# Sonar_2012_V9.net
KiCad netlist of a schematic drawn in EAGLE
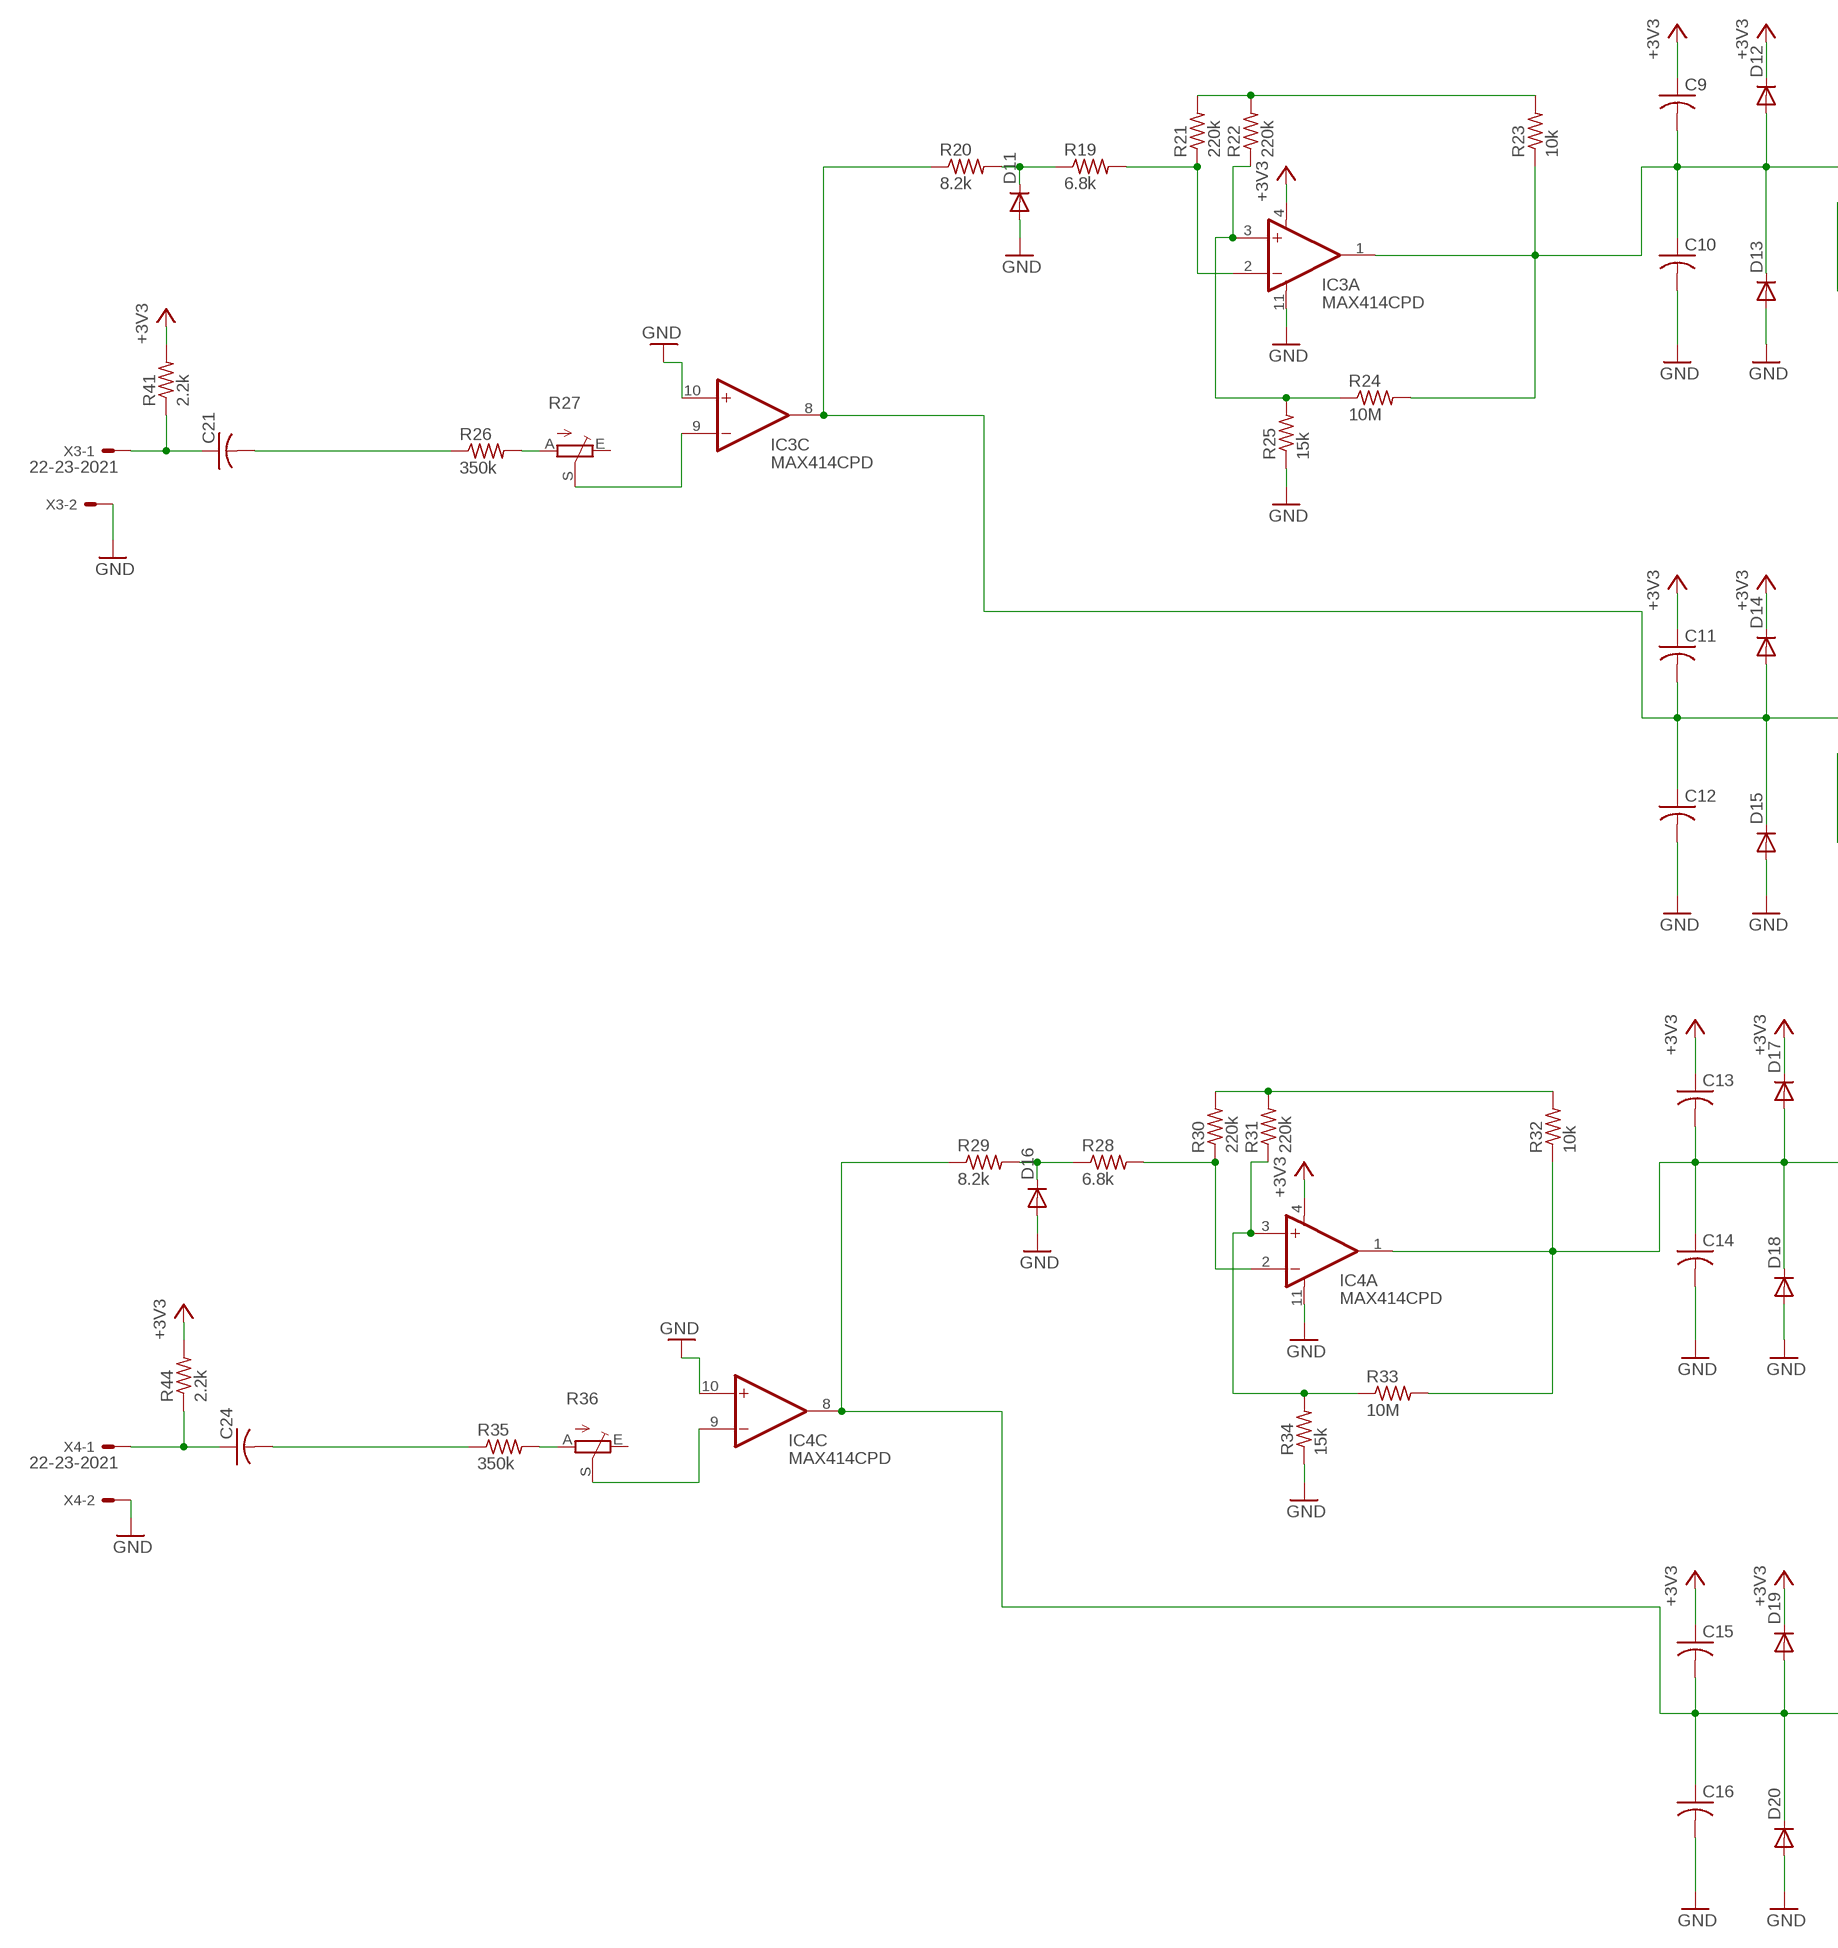
[diagram p0: schematic, sheet 1, part 1 of 2]
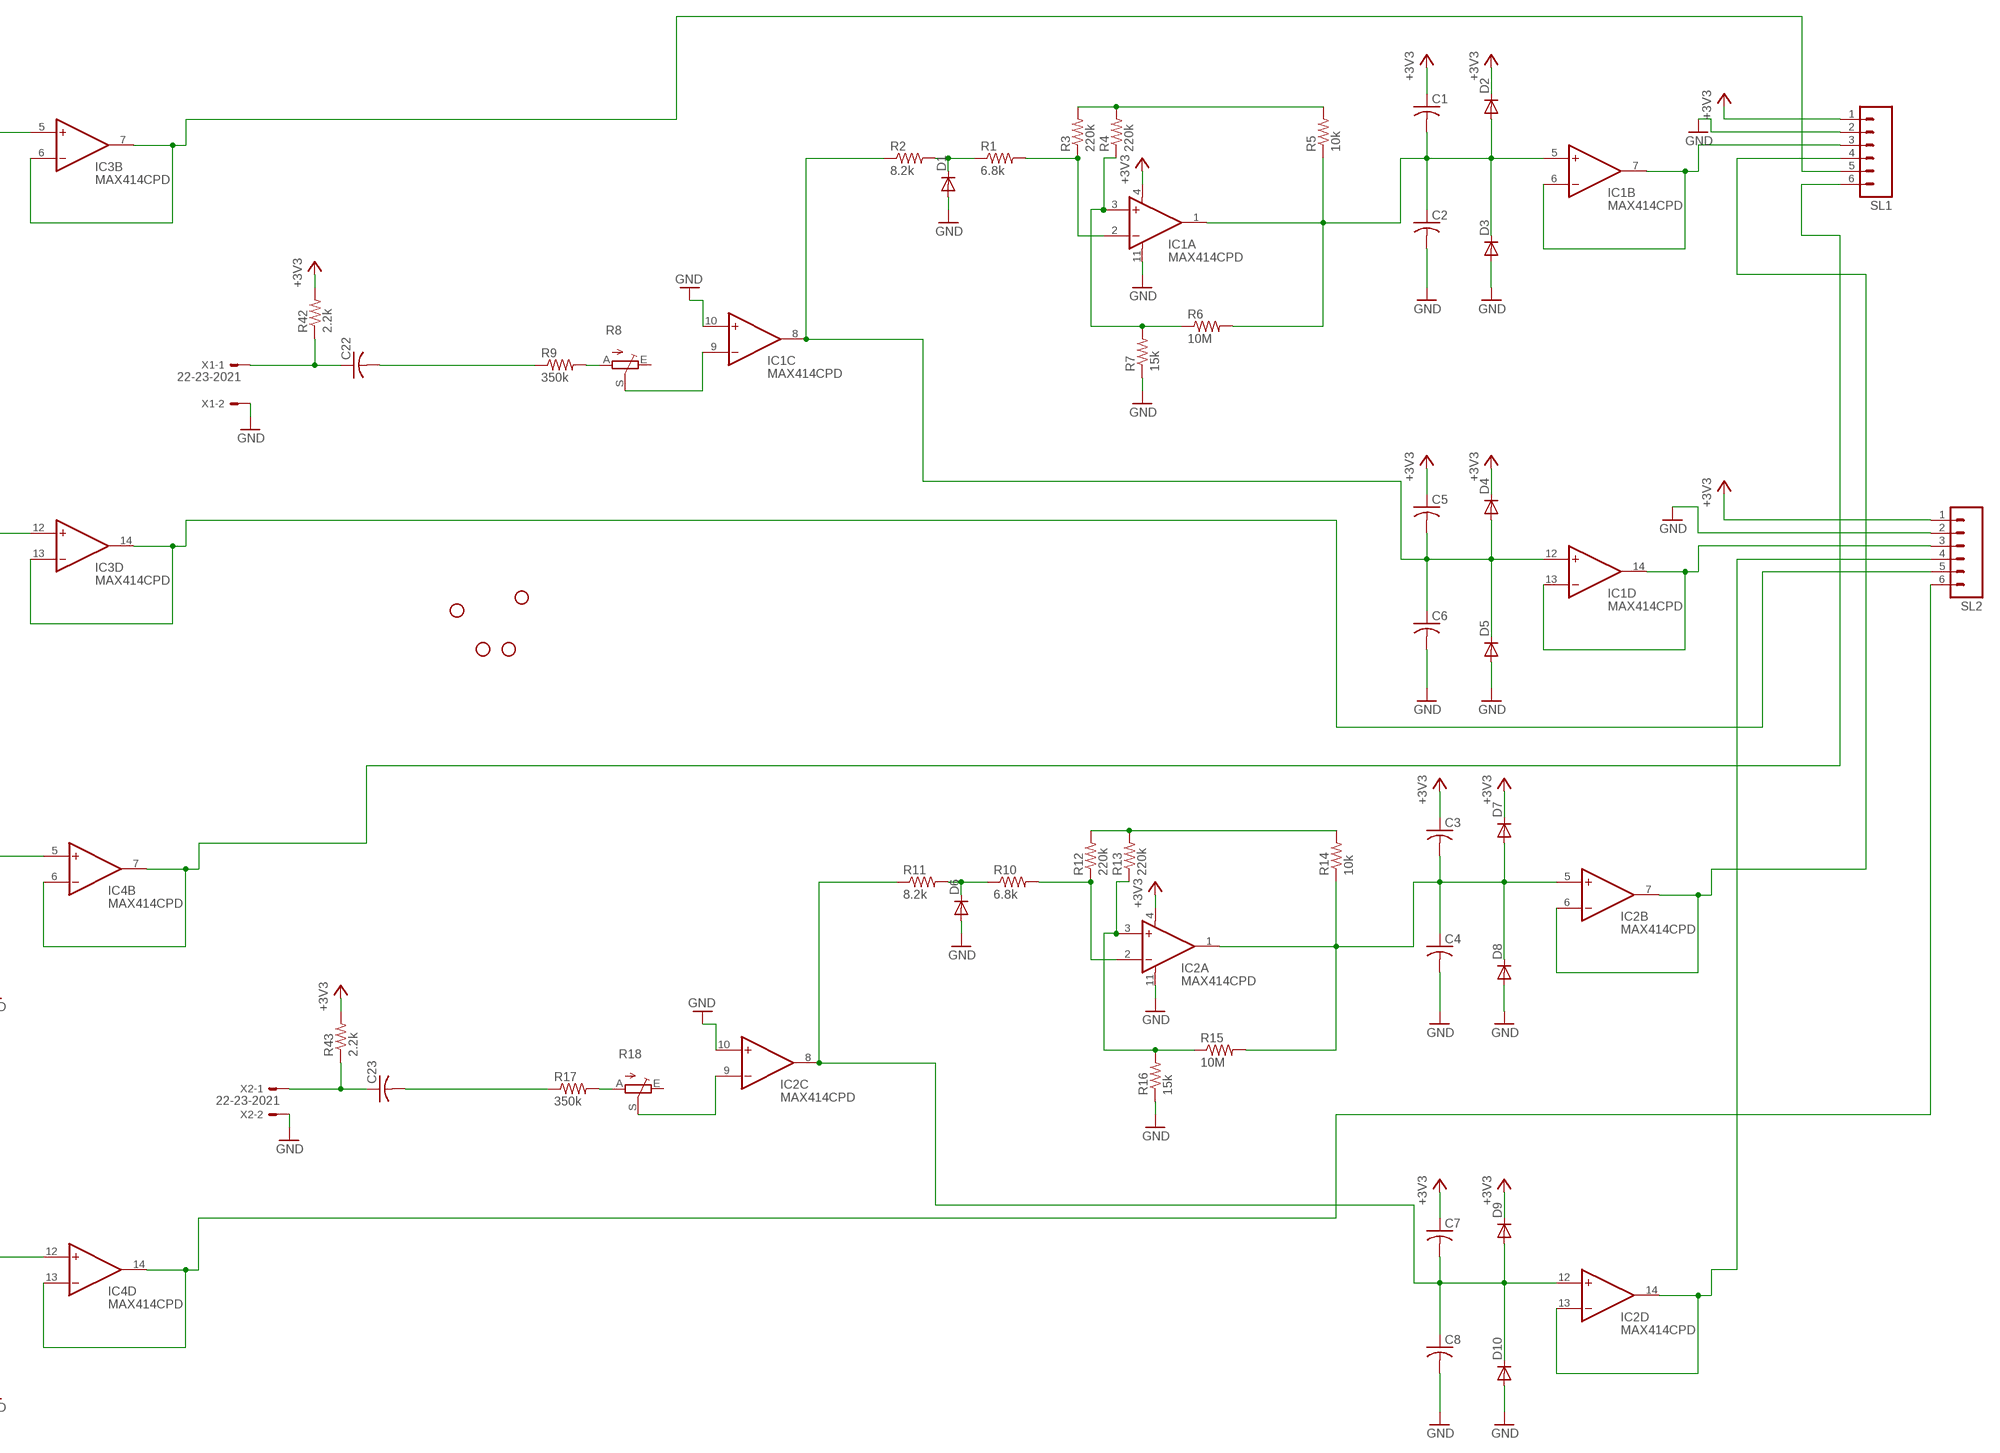
[diagram p1: schematic, sheet 1, part 2 of 2]

(export (version "E")
  (design (tool "Eeschema 10.0.6"))
  (components
    (comp (ref "C1")
      (value "C-USC0603")
      (footprint "eagle-import:C0603")
      (libsource (lib "eagle-import") (part "C-USC0603"))
    )
    (comp (ref "C2")
      (value "C-USC0603")
      (footprint "eagle-import:C0603")
      (libsource (lib "eagle-import") (part "C-USC0603"))
    )
    (comp (ref "C3")
      (value "C-USC0603")
      (footprint "eagle-import:C0603")
      (libsource (lib "eagle-import") (part "C-USC0603"))
    )
    (comp (ref "C4")
      (value "C-USC0603")
      (footprint "eagle-import:C0603")
      (libsource (lib "eagle-import") (part "C-USC0603"))
    )
    (comp (ref "C5")
      (value "C-USC0603")
      (footprint "eagle-import:C0603")
      (libsource (lib "eagle-import") (part "C-USC0603"))
    )
    (comp (ref "C6")
      (value "C-USC0603")
      (footprint "eagle-import:C0603")
      (libsource (lib "eagle-import") (part "C-USC0603"))
    )
    (comp (ref "C7")
      (value "C-USC0603")
      (footprint "eagle-import:C0603")
      (libsource (lib "eagle-import") (part "C-USC0603"))
    )
    (comp (ref "C8")
      (value "C-USC0603")
      (footprint "eagle-import:C0603")
      (libsource (lib "eagle-import") (part "C-USC0603"))
    )
    (comp (ref "C9")
      (value "C-USC0603")
      (footprint "eagle-import:C0603")
      (libsource (lib "eagle-import") (part "C-USC0603"))
    )
    (comp (ref "C10")
      (value "C-USC0603")
      (footprint "eagle-import:C0603")
      (libsource (lib "eagle-import") (part "C-USC0603"))
    )
    (comp (ref "C11")
      (value "C-USC0603")
      (footprint "eagle-import:C0603")
      (libsource (lib "eagle-import") (part "C-USC0603"))
    )
    (comp (ref "C12")
      (value "C-USC0603")
      (footprint "eagle-import:C0603")
      (libsource (lib "eagle-import") (part "C-USC0603"))
    )
    (comp (ref "C13")
      (value "C-USC0603")
      (footprint "eagle-import:C0603")
      (libsource (lib "eagle-import") (part "C-USC0603"))
    )
    (comp (ref "C14")
      (value "C-USC0603")
      (footprint "eagle-import:C0603")
      (libsource (lib "eagle-import") (part "C-USC0603"))
    )
    (comp (ref "C15")
      (value "C-USC0603")
      (footprint "eagle-import:C0603")
      (libsource (lib "eagle-import") (part "C-USC0603"))
    )
    (comp (ref "C16")
      (value "C-USC0603")
      (footprint "eagle-import:C0603")
      (libsource (lib "eagle-import") (part "C-USC0603"))
    )
    (comp (ref "C21")
      (value "C-USC0603")
      (footprint "eagle-import:C0603")
      (libsource (lib "eagle-import") (part "C-USC0603"))
    )
    (comp (ref "C22")
      (value "C-USC0603")
      (footprint "eagle-import:C0603")
      (libsource (lib "eagle-import") (part "C-USC0603"))
    )
    (comp (ref "C23")
      (value "C-USC0603")
      (footprint "eagle-import:C0603")
      (libsource (lib "eagle-import") (part "C-USC0603"))
    )
    (comp (ref "C24")
      (value "C-USC0603")
      (footprint "eagle-import:C0603")
      (libsource (lib "eagle-import") (part "C-USC0603"))
    )
    (comp (ref "D1")
      (value "DIODE-SOD523")
      (footprint "eagle-import:SOD523")
      (libsource (lib "eagle-import") (part "DIODE-SOD523"))
    )
    (comp (ref "D2")
      (value "DIODE-SOD523")
      (footprint "eagle-import:SOD523")
      (libsource (lib "eagle-import") (part "DIODE-SOD523"))
    )
    (comp (ref "D3")
      (value "DIODE-SOD523")
      (footprint "eagle-import:SOD523")
      (libsource (lib "eagle-import") (part "DIODE-SOD523"))
    )
    (comp (ref "D4")
      (value "DIODE-SOD523")
      (footprint "eagle-import:SOD523")
      (libsource (lib "eagle-import") (part "DIODE-SOD523"))
    )
    (comp (ref "D5")
      (value "DIODE-SOD523")
      (footprint "eagle-import:SOD523")
      (libsource (lib "eagle-import") (part "DIODE-SOD523"))
    )
    (comp (ref "D6")
      (value "DIODE-SOD523")
      (footprint "eagle-import:SOD523")
      (libsource (lib "eagle-import") (part "DIODE-SOD523"))
    )
    (comp (ref "D7")
      (value "DIODE-SOD523")
      (footprint "eagle-import:SOD523")
      (libsource (lib "eagle-import") (part "DIODE-SOD523"))
    )
    (comp (ref "D8")
      (value "DIODE-SOD523")
      (footprint "eagle-import:SOD523")
      (libsource (lib "eagle-import") (part "DIODE-SOD523"))
    )
    (comp (ref "D9")
      (value "DIODE-SOD523")
      (footprint "eagle-import:SOD523")
      (libsource (lib "eagle-import") (part "DIODE-SOD523"))
    )
    (comp (ref "D10")
      (value "DIODE-SOD523")
      (footprint "eagle-import:SOD523")
      (libsource (lib "eagle-import") (part "DIODE-SOD523"))
    )
    (comp (ref "D11")
      (value "DIODE-SOD523")
      (footprint "eagle-import:SOD523")
      (libsource (lib "eagle-import") (part "DIODE-SOD523"))
    )
    (comp (ref "D12")
      (value "DIODE-SOD523")
      (footprint "eagle-import:SOD523")
      (libsource (lib "eagle-import") (part "DIODE-SOD523"))
    )
    (comp (ref "D13")
      (value "DIODE-SOD523")
      (footprint "eagle-import:SOD523")
      (libsource (lib "eagle-import") (part "DIODE-SOD523"))
    )
    (comp (ref "D14")
      (value "DIODE-SOD523")
      (footprint "eagle-import:SOD523")
      (libsource (lib "eagle-import") (part "DIODE-SOD523"))
    )
    (comp (ref "D15")
      (value "DIODE-SOD523")
      (footprint "eagle-import:SOD523")
      (libsource (lib "eagle-import") (part "DIODE-SOD523"))
    )
    (comp (ref "D16")
      (value "DIODE-SOD523")
      (footprint "eagle-import:SOD523")
      (libsource (lib "eagle-import") (part "DIODE-SOD523"))
    )
    (comp (ref "D17")
      (value "DIODE-SOD523")
      (footprint "eagle-import:SOD523")
      (libsource (lib "eagle-import") (part "DIODE-SOD523"))
    )
    (comp (ref "D18")
      (value "DIODE-SOD523")
      (footprint "eagle-import:SOD523")
      (libsource (lib "eagle-import") (part "DIODE-SOD523"))
    )
    (comp (ref "D19")
      (value "DIODE-SOD523")
      (footprint "eagle-import:SOD523")
      (libsource (lib "eagle-import") (part "DIODE-SOD523"))
    )
    (comp (ref "D20")
      (value "DIODE-SOD523")
      (footprint "eagle-import:SOD523")
      (libsource (lib "eagle-import") (part "DIODE-SOD523"))
    )
    (comp (ref "IC1")
      (value "MAX414CPD")
      (footprint "eagle-import:DIL14")
      (fields (field (name "MPN") "MAX414CPD+"))
      (libsource (lib "eagle-import") (part "MAX414CPD"))
    )
    (comp (ref "IC2")
      (value "MAX414CPD")
      (footprint "eagle-import:DIL14")
      (fields (field (name "MPN") "MAX414CPD+"))
      (libsource (lib "eagle-import") (part "MAX414CPD"))
    )
    (comp (ref "IC3")
      (value "MAX414CPD")
      (footprint "eagle-import:DIL14")
      (fields (field (name "MPN") "MAX414CPD+"))
      (libsource (lib "eagle-import") (part "MAX414CPD"))
    )
    (comp (ref "IC4")
      (value "MAX414CPD")
      (footprint "eagle-import:DIL14")
      (fields (field (name "MPN") "MAX414CPD+"))
      (libsource (lib "eagle-import") (part "MAX414CPD"))
    )
    (comp (ref "JP1")
      (value "STAND-OFF")
      (footprint "eagle-import:STAND-OFF")
      (libsource (lib "eagle-import") (part "STAND-OFF"))
    )
    (comp (ref "JP2")
      (value "STAND-OFF")
      (footprint "eagle-import:STAND-OFF")
      (libsource (lib "eagle-import") (part "STAND-OFF"))
    )
    (comp (ref "JP3")
      (value "STAND-OFF")
      (footprint "eagle-import:STAND-OFF")
      (libsource (lib "eagle-import") (part "STAND-OFF"))
    )
    (comp (ref "JP4")
      (value "STAND-OFF")
      (footprint "eagle-import:STAND-OFF")
      (libsource (lib "eagle-import") (part "STAND-OFF"))
    )
    (comp (ref "R1")
      (value "6.8k")
      (footprint "eagle-import:M1206")
      (libsource (lib "eagle-import") (part "R-US_M1206"))
    )
    (comp (ref "R2")
      (value "8.2k")
      (footprint "eagle-import:M1206")
      (libsource (lib "eagle-import") (part "R-US_M1206"))
    )
    (comp (ref "R3")
      (value "220k")
      (footprint "eagle-import:M1206")
      (libsource (lib "eagle-import") (part "R-US_M1206"))
    )
    (comp (ref "R4")
      (value "220k")
      (footprint "eagle-import:M1206")
      (libsource (lib "eagle-import") (part "R-US_M1206"))
    )
    (comp (ref "R5")
      (value "10k")
      (footprint "eagle-import:M1206")
      (libsource (lib "eagle-import") (part "R-US_M1206"))
    )
    (comp (ref "R6")
      (value "10M")
      (footprint "eagle-import:M1206")
      (libsource (lib "eagle-import") (part "R-US_M1206"))
    )
    (comp (ref "R7")
      (value "15k")
      (footprint "eagle-import:M1206")
      (libsource (lib "eagle-import") (part "R-US_M1206"))
    )
    (comp (ref "R8")
      (value "TRIM_EU-B64Y")
      (footprint "eagle-import:B64Y")
      (libsource (lib "eagle-import") (part "TRIM_EU-B64Y"))
    )
    (comp (ref "R9")
      (value "350k")
      (footprint "eagle-import:M1206")
      (libsource (lib "eagle-import") (part "R-US_M1206"))
    )
    (comp (ref "R10")
      (value "6.8k")
      (footprint "eagle-import:M1206")
      (libsource (lib "eagle-import") (part "R-US_M1206"))
    )
    (comp (ref "R11")
      (value "8.2k")
      (footprint "eagle-import:M1206")
      (libsource (lib "eagle-import") (part "R-US_M1206"))
    )
    (comp (ref "R12")
      (value "220k")
      (footprint "eagle-import:M1206")
      (libsource (lib "eagle-import") (part "R-US_M1206"))
    )
    (comp (ref "R13")
      (value "220k")
      (footprint "eagle-import:M1206")
      (libsource (lib "eagle-import") (part "R-US_M1206"))
    )
    (comp (ref "R14")
      (value "10k")
      (footprint "eagle-import:M1206")
      (libsource (lib "eagle-import") (part "R-US_M1206"))
    )
    (comp (ref "R15")
      (value "10M")
      (footprint "eagle-import:M1206")
      (libsource (lib "eagle-import") (part "R-US_M1206"))
    )
    (comp (ref "R16")
      (value "15k")
      (footprint "eagle-import:M1206")
      (libsource (lib "eagle-import") (part "R-US_M1206"))
    )
    (comp (ref "R17")
      (value "350k")
      (footprint "eagle-import:M1206")
      (libsource (lib "eagle-import") (part "R-US_M1206"))
    )
    (comp (ref "R18")
      (value "TRIM_EU-B64Y")
      (footprint "eagle-import:B64Y")
      (libsource (lib "eagle-import") (part "TRIM_EU-B64Y"))
    )
    (comp (ref "R19")
      (value "6.8k")
      (footprint "eagle-import:M1206")
      (libsource (lib "eagle-import") (part "R-US_M1206"))
    )
    (comp (ref "R20")
      (value "8.2k")
      (footprint "eagle-import:M1206")
      (libsource (lib "eagle-import") (part "R-US_M1206"))
    )
    (comp (ref "R21")
      (value "220k")
      (footprint "eagle-import:M1206")
      (libsource (lib "eagle-import") (part "R-US_M1206"))
    )
    (comp (ref "R22")
      (value "220k")
      (footprint "eagle-import:M1206")
      (libsource (lib "eagle-import") (part "R-US_M1206"))
    )
    (comp (ref "R23")
      (value "10k")
      (footprint "eagle-import:M1206")
      (libsource (lib "eagle-import") (part "R-US_M1206"))
    )
    (comp (ref "R24")
      (value "10M")
      (footprint "eagle-import:M1206")
      (libsource (lib "eagle-import") (part "R-US_M1206"))
    )
    (comp (ref "R25")
      (value "15k")
      (footprint "eagle-import:M1206")
      (libsource (lib "eagle-import") (part "R-US_M1206"))
    )
    (comp (ref "R26")
      (value "350k")
      (footprint "eagle-import:M1206")
      (libsource (lib "eagle-import") (part "R-US_M1206"))
    )
    (comp (ref "R27")
      (value "TRIM_EU-B64Y")
      (footprint "eagle-import:B64Y")
      (libsource (lib "eagle-import") (part "TRIM_EU-B64Y"))
    )
    (comp (ref "R28")
      (value "6.8k")
      (footprint "eagle-import:M1206")
      (libsource (lib "eagle-import") (part "R-US_M1206"))
    )
    (comp (ref "R29")
      (value "8.2k")
      (footprint "eagle-import:M1206")
      (libsource (lib "eagle-import") (part "R-US_M1206"))
    )
    (comp (ref "R30")
      (value "220k")
      (footprint "eagle-import:M1206")
      (libsource (lib "eagle-import") (part "R-US_M1206"))
    )
    (comp (ref "R31")
      (value "220k")
      (footprint "eagle-import:M1206")
      (libsource (lib "eagle-import") (part "R-US_M1206"))
    )
    (comp (ref "R32")
      (value "10k")
      (footprint "eagle-import:M1206")
      (libsource (lib "eagle-import") (part "R-US_M1206"))
    )
    (comp (ref "R33")
      (value "10M")
      (footprint "eagle-import:M1206")
      (libsource (lib "eagle-import") (part "R-US_M1206"))
    )
    (comp (ref "R34")
      (value "15k")
      (footprint "eagle-import:M1206")
      (libsource (lib "eagle-import") (part "R-US_M1206"))
    )
    (comp (ref "R35")
      (value "350k")
      (footprint "eagle-import:M1206")
      (libsource (lib "eagle-import") (part "R-US_M1206"))
    )
    (comp (ref "R36")
      (value "TRIM_EU-B64Y")
      (footprint "eagle-import:B64Y")
      (libsource (lib "eagle-import") (part "TRIM_EU-B64Y"))
    )
    (comp (ref "R41")
      (value "2.2k")
      (footprint "eagle-import:M1206")
      (libsource (lib "eagle-import") (part "R-US_M1206"))
    )
    (comp (ref "R42")
      (value "2.2k")
      (footprint "eagle-import:M1206")
      (libsource (lib "eagle-import") (part "R-US_M1206"))
    )
    (comp (ref "R43")
      (value "2.2k")
      (footprint "eagle-import:M1206")
      (libsource (lib "eagle-import") (part "R-US_M1206"))
    )
    (comp (ref "R44")
      (value "2.2k")
      (footprint "eagle-import:M1206")
      (libsource (lib "eagle-import") (part "R-US_M1206"))
    )
    (comp (ref "SL1")
      (value "M06")
      (footprint "eagle-import:06P")
      (libsource (lib "eagle-import") (part "M06"))
    )
    (comp (ref "SL2")
      (value "M06")
      (footprint "eagle-import:06P")
      (libsource (lib "eagle-import") (part "M06"))
    )
    (comp (ref "X1")
      (value "22-23-2021")
      (footprint "eagle-import:22-23-2021")
      (fields (field (name "MF") "MOLEX"))
      (libsource (lib "eagle-import") (part "22-23-2021"))
    )
    (comp (ref "X2")
      (value "22-23-2021")
      (footprint "eagle-import:22-23-2021")
      (fields (field (name "MF") "MOLEX"))
      (libsource (lib "eagle-import") (part "22-23-2021"))
    )
    (comp (ref "X3")
      (value "22-23-2021")
      (footprint "eagle-import:22-23-2021")
      (fields (field (name "MF") "MOLEX"))
      (libsource (lib "eagle-import") (part "22-23-2021"))
    )
    (comp (ref "X4")
      (value "22-23-2021")
      (footprint "eagle-import:22-23-2021")
      (fields (field (name "MF") "MOLEX"))
      (libsource (lib "eagle-import") (part "22-23-2021"))
    )
  )
  (nets
    (net (code "1") (name "+3V3") (class "Default")
      (node (ref "C1") (pin "1") (pinfunction "1_1") (pintype "passive"))
      (node (ref "C11") (pin "1") (pinfunction "1_1") (pintype "passive"))
      (node (ref "C13") (pin "1") (pinfunction "1_1") (pintype "passive"))
      (node (ref "C15") (pin "1") (pinfunction "1_1") (pintype "passive"))
      (node (ref "C3") (pin "1") (pinfunction "1_1") (pintype "passive"))
      (node (ref "C5") (pin "1") (pinfunction "1_1") (pintype "passive"))
      (node (ref "C7") (pin "1") (pinfunction "1_1") (pintype "passive"))
      (node (ref "C9") (pin "1") (pinfunction "1_1") (pintype "passive"))
      (node (ref "D12") (pin "C") (pinfunction "C_C") (pintype "passive"))
      (node (ref "D14") (pin "C") (pinfunction "C_C") (pintype "passive"))
      (node (ref "D17") (pin "C") (pinfunction "C_C") (pintype "passive"))
      (node (ref "D19") (pin "C") (pinfunction "C_C") (pintype "passive"))
      (node (ref "D2") (pin "C") (pinfunction "C_C") (pintype "passive"))
      (node (ref "D4") (pin "C") (pinfunction "C_C") (pintype "passive"))
      (node (ref "D7") (pin "C") (pinfunction "C_C") (pintype "passive"))
      (node (ref "D9") (pin "C") (pinfunction "C_C") (pintype "passive"))
      (node (ref "IC1") (pin "4") (pinfunction "V+_4") (pintype "power_in"))
      (node (ref "IC2") (pin "4") (pinfunction "V+_4") (pintype "power_in"))
      (node (ref "IC3") (pin "4") (pinfunction "V+_4") (pintype "power_in"))
      (node (ref "IC4") (pin "4") (pinfunction "V+_4") (pintype "power_in"))
      (node (ref "R41") (pin "2") (pinfunction "2_2") (pintype "passive"))
      (node (ref "R42") (pin "2") (pinfunction "2_2") (pintype "passive"))
      (node (ref "R43") (pin "2") (pinfunction "2_2") (pintype "passive"))
      (node (ref "R44") (pin "2") (pinfunction "2_2") (pintype "passive"))
      (node (ref "SL1") (pin "1") (pinfunction "1_1") (pintype "passive"))
      (node (ref "SL2") (pin "1") (pinfunction "1_1") (pintype "passive"))
    )
    (net (code "2") (name "GND") (class "Default")
      (node (ref "C10") (pin "2") (pinfunction "2_2") (pintype "passive"))
      (node (ref "C12") (pin "2") (pinfunction "2_2") (pintype "passive"))
      (node (ref "C14") (pin "2") (pinfunction "2_2") (pintype "passive"))
      (node (ref "C16") (pin "2") (pinfunction "2_2") (pintype "passive"))
      (node (ref "C2") (pin "2") (pinfunction "2_2") (pintype "passive"))
      (node (ref "C4") (pin "2") (pinfunction "2_2") (pintype "passive"))
      (node (ref "C6") (pin "2") (pinfunction "2_2") (pintype "passive"))
      (node (ref "C8") (pin "2") (pinfunction "2_2") (pintype "passive"))
      (node (ref "D1") (pin "A") (pinfunction "A_A") (pintype "passive"))
      (node (ref "D10") (pin "A") (pinfunction "A_A") (pintype "passive"))
      (node (ref "D11") (pin "A") (pinfunction "A_A") (pintype "passive"))
      (node (ref "D13") (pin "A") (pinfunction "A_A") (pintype "passive"))
      (node (ref "D15") (pin "A") (pinfunction "A_A") (pintype "passive"))
      (node (ref "D16") (pin "A") (pinfunction "A_A") (pintype "passive"))
      (node (ref "D18") (pin "A") (pinfunction "A_A") (pintype "passive"))
      (node (ref "D20") (pin "A") (pinfunction "A_A") (pintype "passive"))
      (node (ref "D3") (pin "A") (pinfunction "A_A") (pintype "passive"))
      (node (ref "D5") (pin "A") (pinfunction "A_A") (pintype "passive"))
      (node (ref "D6") (pin "A") (pinfunction "A_A") (pintype "passive"))
      (node (ref "D8") (pin "A") (pinfunction "A_A") (pintype "passive"))
      (node (ref "IC1") (pin "10") (pinfunction "+IN_10") (pintype "input"))
      (node (ref "IC1") (pin "11") (pinfunction "V-_11") (pintype "power_in"))
      (node (ref "IC2") (pin "10") (pinfunction "+IN_10") (pintype "input"))
      (node (ref "IC2") (pin "11") (pinfunction "V-_11") (pintype "power_in"))
      (node (ref "IC3") (pin "10") (pinfunction "+IN_10") (pintype "input"))
      (node (ref "IC3") (pin "11") (pinfunction "V-_11") (pintype "power_in"))
      (node (ref "IC4") (pin "10") (pinfunction "+IN_10") (pintype "input"))
      (node (ref "IC4") (pin "11") (pinfunction "V-_11") (pintype "power_in"))
      (node (ref "R16") (pin "1") (pinfunction "1_1") (pintype "passive"))
      (node (ref "R25") (pin "1") (pinfunction "1_1") (pintype "passive"))
      (node (ref "R34") (pin "1") (pinfunction "1_1") (pintype "passive"))
      (node (ref "R7") (pin "1") (pinfunction "1_1") (pintype "passive"))
      (node (ref "SL1") (pin "2") (pinfunction "2_2") (pintype "passive"))
      (node (ref "SL2") (pin "2") (pinfunction "2_2") (pintype "passive"))
      (node (ref "X1") (pin "2") (pinfunction "S_2") (pintype "passive"))
      (node (ref "X2") (pin "2") (pinfunction "S_2") (pintype "passive"))
      (node (ref "X3") (pin "2") (pinfunction "S_2") (pintype "passive"))
      (node (ref "X4") (pin "2") (pinfunction "S_2") (pintype "passive"))
    )
    (net (code "3") (name "Net-(C21-Pad2)") (class "Default")
      (node (ref "C21") (pin "2") (pinfunction "2_2") (pintype "passive"))
      (node (ref "R26") (pin "1") (pinfunction "1_1") (pintype "passive"))
    )
    (net (code "4") (name "Net-(C22-Pad2)") (class "Default")
      (node (ref "C22") (pin "2") (pinfunction "2_2") (pintype "passive"))
      (node (ref "R9") (pin "1") (pinfunction "1_1") (pintype "passive"))
    )
    (net (code "5") (name "Net-(C23-Pad2)") (class "Default")
      (node (ref "C23") (pin "2") (pinfunction "2_2") (pintype "passive"))
      (node (ref "R17") (pin "1") (pinfunction "1_1") (pintype "passive"))
    )
    (net (code "6") (name "Net-(C24-Pad2)") (class "Default")
      (node (ref "C24") (pin "2") (pinfunction "2_2") (pintype "passive"))
      (node (ref "R35") (pin "1") (pinfunction "1_1") (pintype "passive"))
    )
    (net (code "7") (name "Net-(D1-PadC)") (class "Default")
      (node (ref "D1") (pin "C") (pinfunction "C_C") (pintype "passive"))
      (node (ref "R1") (pin "1") (pinfunction "1_1") (pintype "passive"))
      (node (ref "R2") (pin "2") (pinfunction "2_2") (pintype "passive"))
    )
    (net (code "8") (name "Net-(D6-PadC)") (class "Default")
      (node (ref "D6") (pin "C") (pinfunction "C_C") (pintype "passive"))
      (node (ref "R10") (pin "1") (pinfunction "1_1") (pintype "passive"))
      (node (ref "R11") (pin "2") (pinfunction "2_2") (pintype "passive"))
    )
    (net (code "9") (name "Net-(D11-PadC)") (class "Default")
      (node (ref "D11") (pin "C") (pinfunction "C_C") (pintype "passive"))
      (node (ref "R19") (pin "1") (pinfunction "1_1") (pintype "passive"))
      (node (ref "R20") (pin "2") (pinfunction "2_2") (pintype "passive"))
    )
    (net (code "10") (name "Net-(D16-PadC)") (class "Default")
      (node (ref "D16") (pin "C") (pinfunction "C_C") (pintype "passive"))
      (node (ref "R28") (pin "1") (pinfunction "1_1") (pintype "passive"))
      (node (ref "R29") (pin "2") (pinfunction "2_2") (pintype "passive"))
    )
    (net (code "11") (name "Net-(IC1A-+IN)") (class "Default")
      (node (ref "IC1") (pin "3") (pinfunction "+IN_3") (pintype "input"))
      (node (ref "R4") (pin "1") (pinfunction "1_1") (pintype "passive"))
      (node (ref "R6") (pin "1") (pinfunction "1_1") (pintype "passive"))
      (node (ref "R7") (pin "2") (pinfunction "2_2") (pintype "passive"))
    )
    (net (code "12") (name "Net-(IC1A--IN)") (class "Default")
      (node (ref "IC1") (pin "2") (pinfunction "-IN_2") (pintype "input"))
      (node (ref "R1") (pin "2") (pinfunction "2_2") (pintype "passive"))
      (node (ref "R3") (pin "1") (pinfunction "1_1") (pintype "passive"))
    )
    (net (code "13") (name "Net-(IC1A-OUT)") (class "Default")
      (node (ref "C1") (pin "2") (pinfunction "2_2") (pintype "passive"))
      (node (ref "C2") (pin "1") (pinfunction "1_1") (pintype "passive"))
      (node (ref "D2") (pin "A") (pinfunction "A_A") (pintype "passive"))
      (node (ref "D3") (pin "C") (pinfunction "C_C") (pintype "passive"))
      (node (ref "IC1") (pin "1") (pinfunction "OUT_1") (pintype "output"))
      (node (ref "IC1") (pin "5") (pinfunction "+IN_5") (pintype "input"))
      (node (ref "R5") (pin "1") (pinfunction "1_1") (pintype "passive"))
      (node (ref "R6") (pin "2") (pinfunction "2_2") (pintype "passive"))
    )
    (net (code "14") (name "Net-(IC1B--IN)") (class "Default")
      (node (ref "IC1") (pin "6") (pinfunction "-IN_6") (pintype "input"))
      (node (ref "IC1") (pin "7") (pinfunction "OUT_7") (pintype "output"))
      (node (ref "SL1") (pin "3") (pinfunction "3_3") (pintype "passive"))
    )
    (net (code "15") (name "Net-(IC1C--IN)") (class "Default")
      (node (ref "IC1") (pin "9") (pinfunction "-IN_9") (pintype "input"))
      (node (ref "R8") (pin "S") (pinfunction "S_S") (pintype "passive"))
    )
    (net (code "16") (name "Net-(IC1C-OUT)") (class "Default")
      (node (ref "C5") (pin "2") (pinfunction "2_2") (pintype "passive"))
      (node (ref "C6") (pin "1") (pinfunction "1_1") (pintype "passive"))
      (node (ref "D4") (pin "A") (pinfunction "A_A") (pintype "passive"))
      (node (ref "D5") (pin "C") (pinfunction "C_C") (pintype "passive"))
      (node (ref "IC1") (pin "12") (pinfunction "+IN_12") (pintype "input"))
      (node (ref "IC1") (pin "8") (pinfunction "OUT_8") (pintype "output"))
      (node (ref "R2") (pin "1") (pinfunction "1_1") (pintype "passive"))
    )
    (net (code "17") (name "Net-(IC1D--IN)") (class "Default")
      (node (ref "IC1") (pin "13") (pinfunction "-IN_13") (pintype "input"))
      (node (ref "IC1") (pin "14") (pinfunction "OUT_14") (pintype "output"))
      (node (ref "SL2") (pin "3") (pinfunction "3_3") (pintype "passive"))
    )
    (net (code "18") (name "Net-(IC2A-+IN)") (class "Default")
      (node (ref "IC2") (pin "3") (pinfunction "+IN_3") (pintype "input"))
      (node (ref "R13") (pin "1") (pinfunction "1_1") (pintype "passive"))
      (node (ref "R15") (pin "1") (pinfunction "1_1") (pintype "passive"))
      (node (ref "R16") (pin "2") (pinfunction "2_2") (pintype "passive"))
    )
    (net (code "19") (name "Net-(IC2A--IN)") (class "Default")
      (node (ref "IC2") (pin "2") (pinfunction "-IN_2") (pintype "input"))
      (node (ref "R10") (pin "2") (pinfunction "2_2") (pintype "passive"))
      (node (ref "R12") (pin "1") (pinfunction "1_1") (pintype "passive"))
    )
    (net (code "20") (name "Net-(IC2A-OUT)") (class "Default")
      (node (ref "C3") (pin "2") (pinfunction "2_2") (pintype "passive"))
      (node (ref "C4") (pin "1") (pinfunction "1_1") (pintype "passive"))
      (node (ref "D7") (pin "A") (pinfunction "A_A") (pintype "passive"))
      (node (ref "D8") (pin "C") (pinfunction "C_C") (pintype "passive"))
      (node (ref "IC2") (pin "1") (pinfunction "OUT_1") (pintype "output"))
      (node (ref "IC2") (pin "5") (pinfunction "+IN_5") (pintype "input"))
      (node (ref "R14") (pin "1") (pinfunction "1_1") (pintype "passive"))
      (node (ref "R15") (pin "2") (pinfunction "2_2") (pintype "passive"))
    )
    (net (code "21") (name "Net-(IC2B--IN)") (class "Default")
      (node (ref "IC2") (pin "6") (pinfunction "-IN_6") (pintype "input"))
      (node (ref "IC2") (pin "7") (pinfunction "OUT_7") (pintype "output"))
      (node (ref "SL1") (pin "4") (pinfunction "4_4") (pintype "passive"))
    )
    (net (code "22") (name "Net-(IC2C--IN)") (class "Default")
      (node (ref "IC2") (pin "9") (pinfunction "-IN_9") (pintype "input"))
      (node (ref "R18") (pin "S") (pinfunction "S_S") (pintype "passive"))
    )
    (net (code "23") (name "Net-(IC2C-OUT)") (class "Default")
      (node (ref "C7") (pin "2") (pinfunction "2_2") (pintype "passive"))
      (node (ref "C8") (pin "1") (pinfunction "1_1") (pintype "passive"))
      (node (ref "D10") (pin "C") (pinfunction "C_C") (pintype "passive"))
      (node (ref "D9") (pin "A") (pinfunction "A_A") (pintype "passive"))
      (node (ref "IC2") (pin "12") (pinfunction "+IN_12") (pintype "input"))
      (node (ref "IC2") (pin "8") (pinfunction "OUT_8") (pintype "output"))
      (node (ref "R11") (pin "1") (pinfunction "1_1") (pintype "passive"))
    )
    (net (code "24") (name "Net-(IC2D--IN)") (class "Default")
      (node (ref "IC2") (pin "13") (pinfunction "-IN_13") (pintype "input"))
      (node (ref "IC2") (pin "14") (pinfunction "OUT_14") (pintype "output"))
      (node (ref "SL2") (pin "4") (pinfunction "4_4") (pintype "passive"))
    )
    (net (code "25") (name "Net-(IC3A-+IN)") (class "Default")
      (node (ref "IC3") (pin "3") (pinfunction "+IN_3") (pintype "input"))
      (node (ref "R22") (pin "1") (pinfunction "1_1") (pintype "passive"))
      (node (ref "R24") (pin "1") (pinfunction "1_1") (pintype "passive"))
      (node (ref "R25") (pin "2") (pinfunction "2_2") (pintype "passive"))
    )
    (net (code "26") (name "Net-(IC3A--IN)") (class "Default")
      (node (ref "IC3") (pin "2") (pinfunction "-IN_2") (pintype "input"))
      (node (ref "R19") (pin "2") (pinfunction "2_2") (pintype "passive"))
      (node (ref "R21") (pin "1") (pinfunction "1_1") (pintype "passive"))
    )
    (net (code "27") (name "Net-(IC3A-OUT)") (class "Default")
      (node (ref "C10") (pin "1") (pinfunction "1_1") (pintype "passive"))
      (node (ref "C9") (pin "2") (pinfunction "2_2") (pintype "passive"))
      (node (ref "D12") (pin "A") (pinfunction "A_A") (pintype "passive"))
      (node (ref "D13") (pin "C") (pinfunction "C_C") (pintype "passive"))
      (node (ref "IC3") (pin "1") (pinfunction "OUT_1") (pintype "output"))
      (node (ref "IC3") (pin "5") (pinfunction "+IN_5") (pintype "input"))
      (node (ref "R23") (pin "1") (pinfunction "1_1") (pintype "passive"))
      (node (ref "R24") (pin "2") (pinfunction "2_2") (pintype "passive"))
    )
    (net (code "28") (name "Net-(IC3B--IN)") (class "Default")
      (node (ref "IC3") (pin "6") (pinfunction "-IN_6") (pintype "input"))
      (node (ref "IC3") (pin "7") (pinfunction "OUT_7") (pintype "output"))
      (node (ref "SL1") (pin "5") (pinfunction "5_5") (pintype "passive"))
    )
    (net (code "29") (name "Net-(IC3C--IN)") (class "Default")
      (node (ref "IC3") (pin "9") (pinfunction "-IN_9") (pintype "input"))
      (node (ref "R27") (pin "S") (pinfunction "S_S") (pintype "passive"))
    )
    (net (code "30") (name "Net-(IC3C-OUT)") (class "Default")
      (node (ref "C11") (pin "2") (pinfunction "2_2") (pintype "passive"))
      (node (ref "C12") (pin "1") (pinfunction "1_1") (pintype "passive"))
      (node (ref "D14") (pin "A") (pinfunction "A_A") (pintype "passive"))
      (node (ref "D15") (pin "C") (pinfunction "C_C") (pintype "passive"))
      (node (ref "IC3") (pin "12") (pinfunction "+IN_12") (pintype "input"))
      (node (ref "IC3") (pin "8") (pinfunction "OUT_8") (pintype "output"))
      (node (ref "R20") (pin "1") (pinfunction "1_1") (pintype "passive"))
    )
    (net (code "31") (name "Net-(IC3D--IN)") (class "Default")
      (node (ref "IC3") (pin "13") (pinfunction "-IN_13") (pintype "input"))
      (node (ref "IC3") (pin "14") (pinfunction "OUT_14") (pintype "output"))
      (node (ref "SL2") (pin "5") (pinfunction "5_5") (pintype "passive"))
    )
    (net (code "32") (name "Net-(IC4A-+IN)") (class "Default")
      (node (ref "IC4") (pin "3") (pinfunction "+IN_3") (pintype "input"))
      (node (ref "R31") (pin "1") (pinfunction "1_1") (pintype "passive"))
      (node (ref "R33") (pin "1") (pinfunction "1_1") (pintype "passive"))
      (node (ref "R34") (pin "2") (pinfunction "2_2") (pintype "passive"))
    )
    (net (code "33") (name "Net-(IC4A--IN)") (class "Default")
      (node (ref "IC4") (pin "2") (pinfunction "-IN_2") (pintype "input"))
      (node (ref "R28") (pin "2") (pinfunction "2_2") (pintype "passive"))
      (node (ref "R30") (pin "1") (pinfunction "1_1") (pintype "passive"))
    )
    (net (code "34") (name "Net-(IC4A-OUT)") (class "Default")
      (node (ref "C13") (pin "2") (pinfunction "2_2") (pintype "passive"))
      (node (ref "C14") (pin "1") (pinfunction "1_1") (pintype "passive"))
      (node (ref "D17") (pin "A") (pinfunction "A_A") (pintype "passive"))
      (node (ref "D18") (pin "C") (pinfunction "C_C") (pintype "passive"))
      (node (ref "IC4") (pin "1") (pinfunction "OUT_1") (pintype "output"))
      (node (ref "IC4") (pin "5") (pinfunction "+IN_5") (pintype "input"))
      (node (ref "R32") (pin "1") (pinfunction "1_1") (pintype "passive"))
      (node (ref "R33") (pin "2") (pinfunction "2_2") (pintype "passive"))
    )
    (net (code "35") (name "Net-(IC4B--IN)") (class "Default")
      (node (ref "IC4") (pin "6") (pinfunction "-IN_6") (pintype "input"))
      (node (ref "IC4") (pin "7") (pinfunction "OUT_7") (pintype "output"))
      (node (ref "SL1") (pin "6") (pinfunction "6_6") (pintype "passive"))
    )
    (net (code "36") (name "Net-(IC4C--IN)") (class "Default")
      (node (ref "IC4") (pin "9") (pinfunction "-IN_9") (pintype "input"))
      (node (ref "R36") (pin "S") (pinfunction "S_S") (pintype "passive"))
    )
    (net (code "37") (name "Net-(IC4C-OUT)") (class "Default")
      (node (ref "C15") (pin "2") (pinfunction "2_2") (pintype "passive"))
      (node (ref "C16") (pin "1") (pinfunction "1_1") (pintype "passive"))
      (node (ref "D19") (pin "A") (pinfunction "A_A") (pintype "passive"))
      (node (ref "D20") (pin "C") (pinfunction "C_C") (pintype "passive"))
      (node (ref "IC4") (pin "12") (pinfunction "+IN_12") (pintype "input"))
      (node (ref "IC4") (pin "8") (pinfunction "OUT_8") (pintype "output"))
      (node (ref "R29") (pin "1") (pinfunction "1_1") (pintype "passive"))
    )
    (net (code "38") (name "Net-(IC4D--IN)") (class "Default")
      (node (ref "IC4") (pin "13") (pinfunction "-IN_13") (pintype "input"))
      (node (ref "IC4") (pin "14") (pinfunction "OUT_14") (pintype "output"))
      (node (ref "SL2") (pin "6") (pinfunction "6_6") (pintype "passive"))
    )
    (net (code "39") (name "Net-(R3-Pad2)") (class "Default")
      (node (ref "R3") (pin "2") (pinfunction "2_2") (pintype "passive"))
      (node (ref "R4") (pin "2") (pinfunction "2_2") (pintype "passive"))
      (node (ref "R5") (pin "2") (pinfunction "2_2") (pintype "passive"))
    )
    (net (code "40") (name "Net-(R8-PadA)") (class "Default")
      (node (ref "R8") (pin "A") (pinfunction "A_A") (pintype "passive"))
      (node (ref "R9") (pin "2") (pinfunction "2_2") (pintype "passive"))
    )
    (net (code "41") (name "Net-(R12-Pad2)") (class "Default")
      (node (ref "R12") (pin "2") (pinfunction "2_2") (pintype "passive"))
      (node (ref "R13") (pin "2") (pinfunction "2_2") (pintype "passive"))
      (node (ref "R14") (pin "2") (pinfunction "2_2") (pintype "passive"))
    )
    (net (code "42") (name "Net-(R17-Pad2)") (class "Default")
      (node (ref "R17") (pin "2") (pinfunction "2_2") (pintype "passive"))
      (node (ref "R18") (pin "A") (pinfunction "A_A") (pintype "passive"))
    )
    (net (code "43") (name "Net-(R21-Pad2)") (class "Default")
      (node (ref "R21") (pin "2") (pinfunction "2_2") (pintype "passive"))
      (node (ref "R22") (pin "2") (pinfunction "2_2") (pintype "passive"))
      (node (ref "R23") (pin "2") (pinfunction "2_2") (pintype "passive"))
    )
    (net (code "44") (name "Net-(R26-Pad2)") (class "Default")
      (node (ref "R26") (pin "2") (pinfunction "2_2") (pintype "passive"))
      (node (ref "R27") (pin "A") (pinfunction "A_A") (pintype "passive"))
    )
    (net (code "45") (name "Net-(R30-Pad2)") (class "Default")
      (node (ref "R30") (pin "2") (pinfunction "2_2") (pintype "passive"))
      (node (ref "R31") (pin "2") (pinfunction "2_2") (pintype "passive"))
      (node (ref "R32") (pin "2") (pinfunction "2_2") (pintype "passive"))
    )
    (net (code "46") (name "Net-(R35-Pad2)") (class "Default")
      (node (ref "R35") (pin "2") (pinfunction "2_2") (pintype "passive"))
      (node (ref "R36") (pin "A") (pinfunction "A_A") (pintype "passive"))
    )
    (net (code "47") (name "Net-(X1A-S)") (class "Default")
      (node (ref "C22") (pin "1") (pinfunction "1_1") (pintype "passive"))
      (node (ref "R42") (pin "1") (pinfunction "1_1") (pintype "passive"))
      (node (ref "X1") (pin "1") (pinfunction "S_1") (pintype "passive"))
    )
    (net (code "48") (name "Net-(X2A-S)") (class "Default")
      (node (ref "C23") (pin "1") (pinfunction "1_1") (pintype "passive"))
      (node (ref "R43") (pin "1") (pinfunction "1_1") (pintype "passive"))
      (node (ref "X2") (pin "1") (pinfunction "S_1") (pintype "passive"))
    )
    (net (code "49") (name "Net-(X3A-S)") (class "Default")
      (node (ref "C21") (pin "1") (pinfunction "1_1") (pintype "passive"))
      (node (ref "R41") (pin "1") (pinfunction "1_1") (pintype "passive"))
      (node (ref "X3") (pin "1") (pinfunction "S_1") (pintype "passive"))
    )
    (net (code "50") (name "Net-(X4A-S)") (class "Default")
      (node (ref "C24") (pin "1") (pinfunction "1_1") (pintype "passive"))
      (node (ref "R44") (pin "1") (pinfunction "1_1") (pintype "passive"))
      (node (ref "X4") (pin "1") (pinfunction "S_1") (pintype "passive"))
    )
    (net (code "51") (name "unconnected-(R8-PadE)") (class "Default")
      (node (ref "R8") (pin "E") (pinfunction "E_E") (pintype "passive"))
    )
    (net (code "52") (name "unconnected-(R18-PadE)") (class "Default")
      (node (ref "R18") (pin "E") (pinfunction "E_E") (pintype "passive"))
    )
    (net (code "53") (name "unconnected-(R27-PadE)") (class "Default")
      (node (ref "R27") (pin "E") (pinfunction "E_E") (pintype "passive"))
    )
    (net (code "54") (name "unconnected-(R36-PadE)") (class "Default")
      (node (ref "R36") (pin "E") (pinfunction "E_E") (pintype "passive"))
    )
  )
)
